# tinytx3.net
KiCad netlist of a schematic drawn in EAGLE
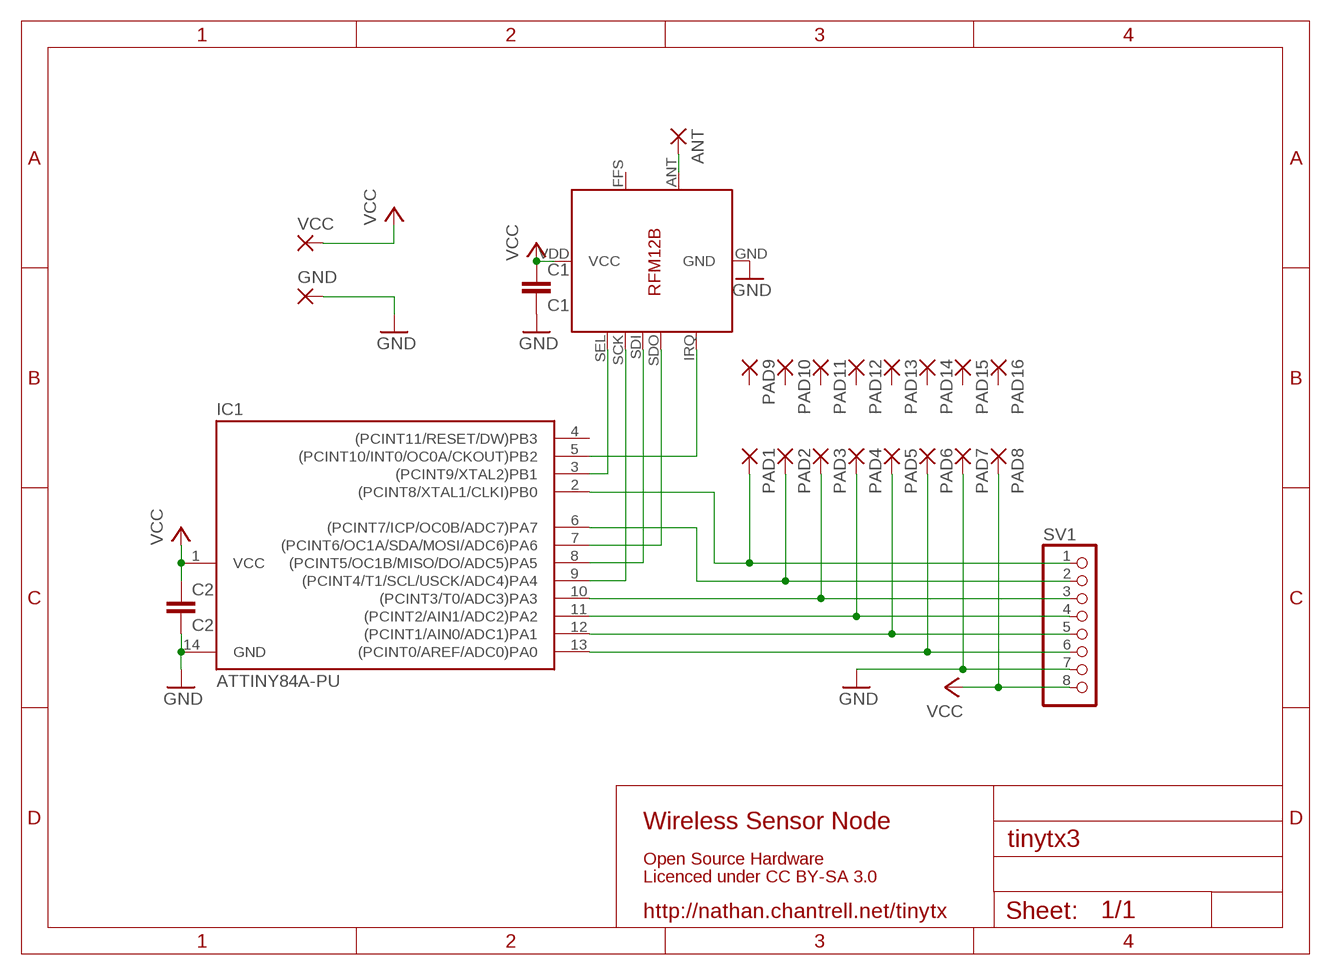
[diagram p0: schematic, sheet 1]

(export (version "E")
  (design (tool "Eeschema 10.0.6"))
  (components
    (comp (ref "ANT")
      (value "1,6/0,8")
      (footprint "eagle-import:1,6_0,8")
      (libsource (lib "eagle-import") (part "1,6/0,8"))
    )
    (comp (ref "C1")
      (value "C1")
      (footprint "eagle-import:C025-025X050")
      (libsource (lib "eagle-import") (part "C-EU025-025X050"))
    )
    (comp (ref "C2")
      (value "C2")
      (footprint "eagle-import:C025-025X050")
      (libsource (lib "eagle-import") (part "C-EU025-025X050"))
    )
    (comp (ref "GND")
      (value "2,15/1,0")
      (footprint "eagle-import:2,15_1,0")
      (libsource (lib "eagle-import") (part "2,15/1,0"))
    )
    (comp (ref "IC1")
      (value "ATTINY84A-PU")
      (footprint "eagle-import:DIL14")
      (libsource (lib "eagle-import") (part "TINY24/44/84-PU"))
    )
    (comp (ref "PAD1")
      (value "1,6/0,9")
      (footprint "eagle-import:1,6_0,9")
      (libsource (lib "eagle-import") (part "1,6/0,9"))
    )
    (comp (ref "PAD2")
      (value "1,6/0,9")
      (footprint "eagle-import:1,6_0,9")
      (libsource (lib "eagle-import") (part "1,6/0,9"))
    )
    (comp (ref "PAD3")
      (value "1,6/0,9")
      (footprint "eagle-import:1,6_0,9")
      (libsource (lib "eagle-import") (part "1,6/0,9"))
    )
    (comp (ref "PAD4")
      (value "1,6/0,9")
      (footprint "eagle-import:1,6_0,9")
      (libsource (lib "eagle-import") (part "1,6/0,9"))
    )
    (comp (ref "PAD5")
      (value "1,6/0,9")
      (footprint "eagle-import:1,6_0,9")
      (libsource (lib "eagle-import") (part "1,6/0,9"))
    )
    (comp (ref "PAD6")
      (value "1,6/0,9")
      (footprint "eagle-import:1,6_0,9")
      (libsource (lib "eagle-import") (part "1,6/0,9"))
    )
    (comp (ref "PAD7")
      (value "1,6/0,9")
      (footprint "eagle-import:1,6_0,9")
      (libsource (lib "eagle-import") (part "1,6/0,9"))
    )
    (comp (ref "PAD8")
      (value "1,6/0,9")
      (footprint "eagle-import:1,6_0,9")
      (libsource (lib "eagle-import") (part "1,6/0,9"))
    )
    (comp (ref "PAD9")
      (value "1,6/0,9")
      (footprint "eagle-import:1,6_0,9")
      (libsource (lib "eagle-import") (part "1,6/0,9"))
    )
    (comp (ref "PAD10")
      (value "1,6/0,9")
      (footprint "eagle-import:1,6_0,9")
      (libsource (lib "eagle-import") (part "1,6/0,9"))
    )
    (comp (ref "PAD11")
      (value "1,6/0,9")
      (footprint "eagle-import:1,6_0,9")
      (libsource (lib "eagle-import") (part "1,6/0,9"))
    )
    (comp (ref "PAD12")
      (value "1,6/0,9")
      (footprint "eagle-import:1,6_0,9")
      (libsource (lib "eagle-import") (part "1,6/0,9"))
    )
    (comp (ref "PAD13")
      (value "1,6/0,9")
      (footprint "eagle-import:1,6_0,9")
      (libsource (lib "eagle-import") (part "1,6/0,9"))
    )
    (comp (ref "PAD14")
      (value "1,6/0,9")
      (footprint "eagle-import:1,6_0,9")
      (libsource (lib "eagle-import") (part "1,6/0,9"))
    )
    (comp (ref "PAD15")
      (value "1,6/0,9")
      (footprint "eagle-import:1,6_0,9")
      (libsource (lib "eagle-import") (part "1,6/0,9"))
    )
    (comp (ref "PAD16")
      (value "1,6/0,9")
      (footprint "eagle-import:1,6_0,9")
      (libsource (lib "eagle-import") (part "1,6/0,9"))
    )
    (comp (ref "SV1")
      (value "PINHD-1X8")
      (footprint "eagle-import:1X08")
      (libsource (lib "eagle-import") (part "PINHD-1X8"))
    )
    (comp (ref "U$1")
      (value "RFM12B")
      (footprint "eagle-import:RFM12B")
      (libsource (lib "eagle-import") (part "RFM12B"))
    )
    (comp (ref "VCC")
      (value "2,15/1,0")
      (footprint "eagle-import:2,15_1,0")
      (libsource (lib "eagle-import") (part "2,15/1,0"))
    )
  )
  (nets
    (net (code "1") (name "GND") (class "Default")
      (node (ref "C1") (pin "2") (pinfunction "2_2") (pintype "passive"))
      (node (ref "C2") (pin "2") (pinfunction "2_2") (pintype "passive"))
      (node (ref "GND") (pin "1") (pinfunction "P_1") (pintype "passive"))
      (node (ref "IC1") (pin "14") (pinfunction "GND_14") (pintype "power_in"))
      (node (ref "PAD7") (pin "1") (pinfunction "P_1") (pintype "passive"))
      (node (ref "SV1") (pin "7") (pinfunction "7_7") (pintype "passive"))
      (node (ref "U$1") (pin "GND") (pinfunction "GND_GND") (pintype "power_in"))
    )
    (net (code "2") (name "Net-(ANT-P)") (class "Default")
      (node (ref "ANT") (pin "1") (pinfunction "P_1") (pintype "passive"))
      (node (ref "U$1") (pin "ANT") (pinfunction "ANT_ANT") (pintype "passive"))
    )
    (net (code "3") (name "Net-(IC1-(PCINT0{slash}AREF{slash}ADC0)PA0)") (class "Default")
      (node (ref "IC1") (pin "13") (pinfunction "(PCINT0/AREF/ADC0)PA0_13") (pintype "bidirectional"))
      (node (ref "PAD6") (pin "1") (pinfunction "P_1") (pintype "passive"))
      (node (ref "SV1") (pin "6") (pinfunction "6_6") (pintype "passive"))
    )
    (net (code "4") (name "Net-(IC1-(PCINT1{slash}AIN0{slash}ADC1)PA1)") (class "Default")
      (node (ref "IC1") (pin "12") (pinfunction "(PCINT1/AIN0/ADC1)PA1_12") (pintype "bidirectional"))
      (node (ref "PAD5") (pin "1") (pinfunction "P_1") (pintype "passive"))
      (node (ref "SV1") (pin "5") (pinfunction "5_5") (pintype "passive"))
    )
    (net (code "5") (name "Net-(IC1-(PCINT2{slash}AIN1{slash}ADC2)PA2)") (class "Default")
      (node (ref "IC1") (pin "11") (pinfunction "(PCINT2/AIN1/ADC2)PA2_11") (pintype "bidirectional"))
      (node (ref "PAD4") (pin "1") (pinfunction "P_1") (pintype "passive"))
      (node (ref "SV1") (pin "4") (pinfunction "4_4") (pintype "passive"))
    )
    (net (code "6") (name "Net-(IC1-(PCINT3{slash}T0{slash}ADC3)PA3)") (class "Default")
      (node (ref "IC1") (pin "10") (pinfunction "(PCINT3/T0/ADC3)PA3_10") (pintype "bidirectional"))
      (node (ref "PAD3") (pin "1") (pinfunction "P_1") (pintype "passive"))
      (node (ref "SV1") (pin "3") (pinfunction "3_3") (pintype "passive"))
    )
    (net (code "7") (name "Net-(IC1-(PCINT4{slash}T1{slash}SCL{slash}USCK{slash}ADC4)PA4)") (class "Default")
      (node (ref "IC1") (pin "9") (pinfunction "(PCINT4/T1/SCL/USCK/ADC4)PA4_9") (pintype "bidirectional"))
      (node (ref "U$1") (pin "SCK") (pinfunction "SCK_SCK") (pintype "input"))
    )
    (net (code "8") (name "Net-(IC1-(PCINT5{slash}OC1B{slash}MISO{slash}DO{slash}ADC5)PA5)") (class "Default")
      (node (ref "IC1") (pin "8") (pinfunction "(PCINT5/OC1B/MISO/DO/ADC5)PA5_8") (pintype "bidirectional"))
      (node (ref "U$1") (pin "SDI") (pinfunction "SDI_SDI") (pintype "input"))
    )
    (net (code "9") (name "Net-(IC1-(PCINT6{slash}OC1A{slash}SDA{slash}MOSI{slash}ADC6)PA6)") (class "Default")
      (node (ref "IC1") (pin "7") (pinfunction "(PCINT6/OC1A/SDA/MOSI/ADC6)PA6_7") (pintype "bidirectional"))
      (node (ref "U$1") (pin "SDO") (pinfunction "SDO_SDO") (pintype "output"))
    )
    (net (code "10") (name "Net-(IC1-(PCINT7{slash}ICP{slash}OC0B{slash}ADC7)PA7)") (class "Default")
      (node (ref "IC1") (pin "6") (pinfunction "(PCINT7/ICP/OC0B/ADC7)PA7_6") (pintype "bidirectional"))
      (node (ref "PAD2") (pin "1") (pinfunction "P_1") (pintype "passive"))
      (node (ref "SV1") (pin "2") (pinfunction "2_2") (pintype "passive"))
    )
    (net (code "11") (name "Net-(IC1-(PCINT8{slash}XTAL1{slash}CLKI)PB0)") (class "Default")
      (node (ref "IC1") (pin "2") (pinfunction "(PCINT8/XTAL1/CLKI)PB0_2") (pintype "bidirectional"))
      (node (ref "PAD1") (pin "1") (pinfunction "P_1") (pintype "passive"))
      (node (ref "SV1") (pin "1") (pinfunction "1_1") (pintype "passive"))
    )
    (net (code "12") (name "Net-(IC1-(PCINT9{slash}XTAL2)PB1)") (class "Default")
      (node (ref "IC1") (pin "3") (pinfunction "(PCINT9/XTAL2)PB1_3") (pintype "bidirectional"))
      (node (ref "U$1") (pin "SEL") (pinfunction "SEL_SEL") (pintype "input"))
    )
    (net (code "13") (name "Net-(IC1-(PCINT10{slash}INT0{slash}OC0A{slash}CKOUT)PB2)") (class "Default")
      (node (ref "IC1") (pin "5") (pinfunction "(PCINT10/INT0/OC0A/CKOUT)PB2_5") (pintype "bidirectional"))
      (node (ref "U$1") (pin "IRQ") (pinfunction "IRQ_IRQ") (pintype "open_collector"))
    )
    (net (code "14") (name "VCC") (class "Default")
      (node (ref "C1") (pin "1") (pinfunction "1_1") (pintype "passive"))
      (node (ref "C2") (pin "1") (pinfunction "1_1") (pintype "passive"))
      (node (ref "IC1") (pin "1") (pinfunction "VCC_1") (pintype "power_in"))
      (node (ref "PAD8") (pin "1") (pinfunction "P_1") (pintype "passive"))
      (node (ref "SV1") (pin "8") (pinfunction "8_8") (pintype "passive"))
      (node (ref "U$1") (pin "VDD") (pinfunction "VCC_VDD") (pintype "power_in"))
      (node (ref "VCC") (pin "1") (pinfunction "P_1") (pintype "passive"))
    )
    (net (code "15") (name "unconnected-(IC1-(PCINT11{slash}RESET{slash}DW)PB3-Pad4)") (class "Default")
      (node (ref "IC1") (pin "4") (pinfunction "(PCINT11/RESET/DW)PB3_4") (pintype "bidirectional"))
    )
    (net (code "16") (name "unconnected-(PAD9-P-Pad1)") (class "Default")
      (node (ref "PAD9") (pin "1") (pinfunction "P_1") (pintype "passive"))
    )
    (net (code "17") (name "unconnected-(PAD10-P-Pad1)") (class "Default")
      (node (ref "PAD10") (pin "1") (pinfunction "P_1") (pintype "passive"))
    )
    (net (code "18") (name "unconnected-(PAD11-P-Pad1)") (class "Default")
      (node (ref "PAD11") (pin "1") (pinfunction "P_1") (pintype "passive"))
    )
    (net (code "19") (name "unconnected-(PAD12-P-Pad1)") (class "Default")
      (node (ref "PAD12") (pin "1") (pinfunction "P_1") (pintype "passive"))
    )
    (net (code "20") (name "unconnected-(PAD13-P-Pad1)") (class "Default")
      (node (ref "PAD13") (pin "1") (pinfunction "P_1") (pintype "passive"))
    )
    (net (code "21") (name "unconnected-(PAD14-P-Pad1)") (class "Default")
      (node (ref "PAD14") (pin "1") (pinfunction "P_1") (pintype "passive"))
    )
    (net (code "22") (name "unconnected-(PAD15-P-Pad1)") (class "Default")
      (node (ref "PAD15") (pin "1") (pinfunction "P_1") (pintype "passive"))
    )
    (net (code "23") (name "unconnected-(PAD16-P-Pad1)") (class "Default")
      (node (ref "PAD16") (pin "1") (pinfunction "P_1") (pintype "passive"))
    )
    (net (code "24") (name "unconnected-(U$1-PadFFS)") (class "Default")
      (node (ref "U$1") (pin "FFS") (pinfunction "FFS_FFS") (pintype "bidirectional"))
    )
  )
)
